# Edison_Mezzanine_I2C_Breakout.net
KiCad netlist of a schematic drawn in EAGLE
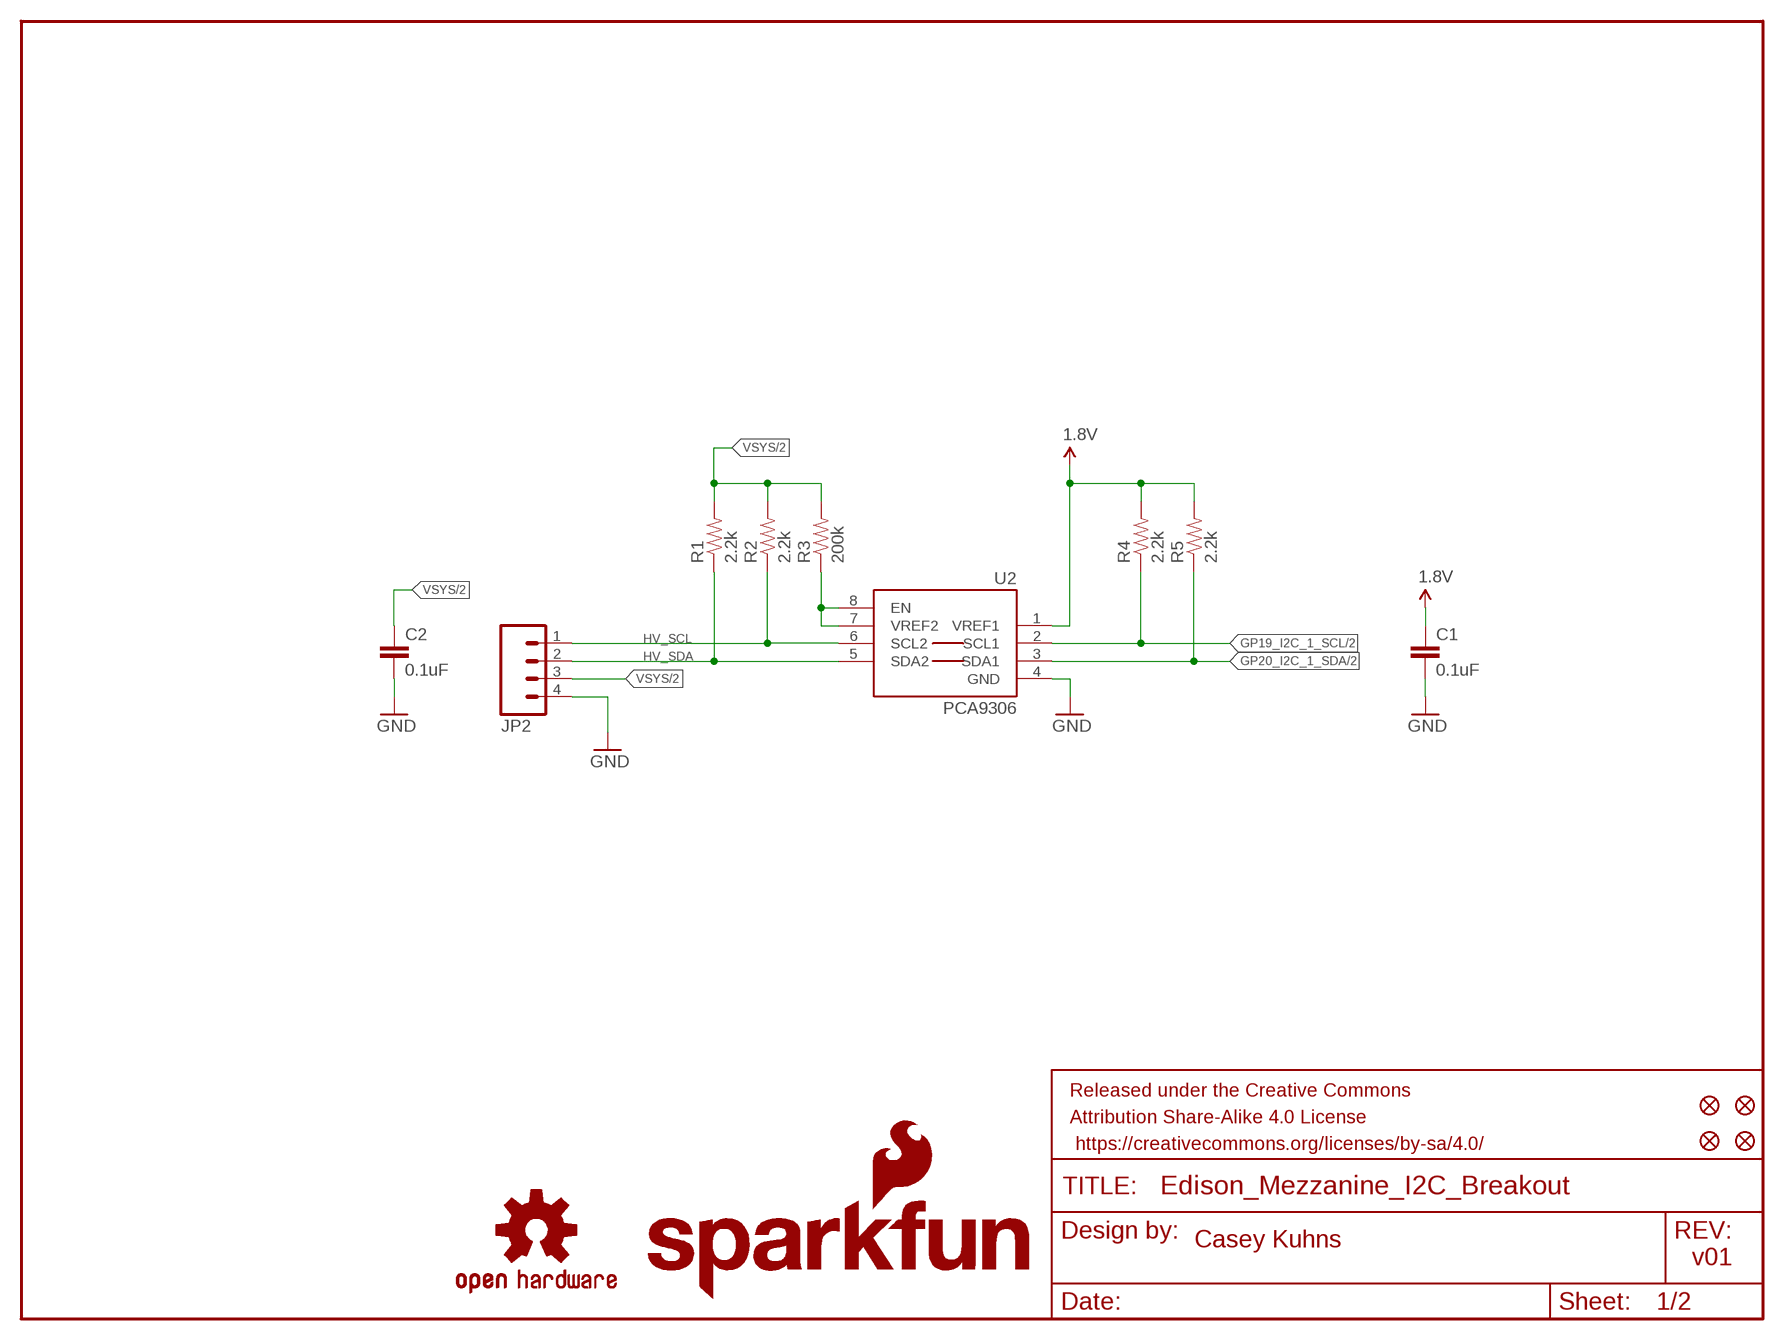
[diagram p0: schematic, sheet 1]
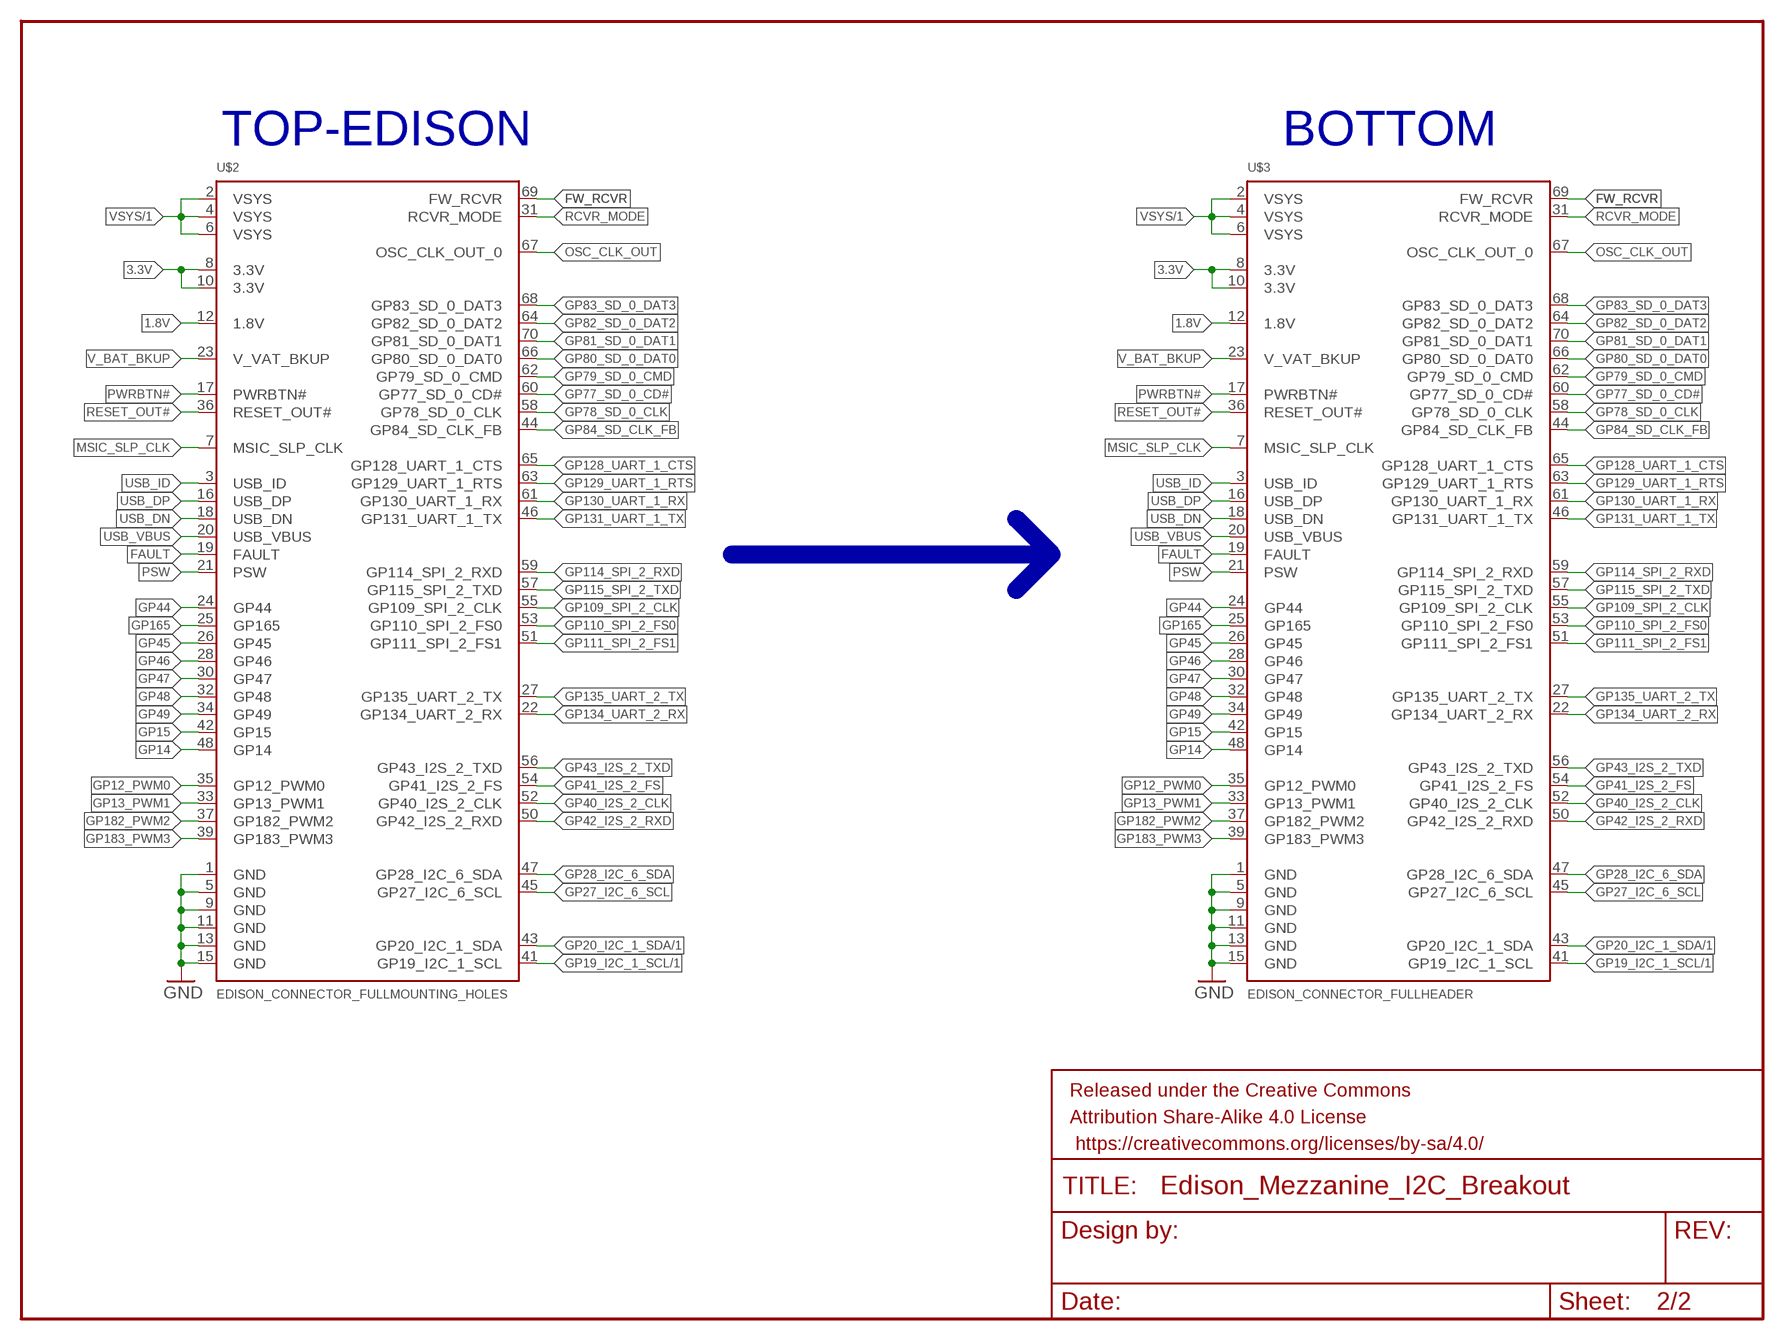
[diagram p1: schematic, sheet 2]

(export (version "E")
  (design (tool "Eeschema 10.0.6"))
  (components
    (comp (ref "C1")
      (value "0.1uF")
      (footprint "eagle-import:0603-CAP")
      (libsource (lib "eagle-import") (part "0.1UF-25V(+80/-20%)(0603)"))
    )
    (comp (ref "C2")
      (value "0.1uF")
      (footprint "eagle-import:0603-CAP")
      (libsource (lib "eagle-import") (part "0.1UF-25V(+80/-20%)(0603)"))
    )
    (comp (ref "FID1")
      (value "FIDUCIAL1X2")
      (footprint "eagle-import:FIDUCIAL-1X2")
      (libsource (lib "eagle-import") (part "FIDUCIAL1X2"))
    )
    (comp (ref "FID2")
      (value "FIDUCIAL1X2")
      (footprint "eagle-import:FIDUCIAL-1X2")
      (libsource (lib "eagle-import") (part "FIDUCIAL1X2"))
    )
    (comp (ref "FID3")
      (value "FIDUCIAL1X2")
      (footprint "eagle-import:FIDUCIAL-1X2")
      (libsource (lib "eagle-import") (part "FIDUCIAL1X2"))
    )
    (comp (ref "FID4")
      (value "FIDUCIAL1X2")
      (footprint "eagle-import:FIDUCIAL-1X2")
      (libsource (lib "eagle-import") (part "FIDUCIAL1X2"))
    )
    (comp (ref "FRAME1")
      (value "FRAME-LETTER")
      (footprint "eagle-import:CREATIVE_COMMONS")
      (libsource (lib "eagle-import") (part "FRAME-LETTER"))
    )
    (comp (ref "JP2")
      (value "M04SMD_RA_FEMALE")
      (footprint "eagle-import:1X04_SMD_RA_FEMALE")
      (libsource (lib "eagle-import") (part "M04SMD_RA_FEMALE"))
    )
    (comp (ref "LOGO1")
      (value "SFE_LOGO_NAME_FLAME.1_INCH")
      (footprint "eagle-import:SFE_LOGO_NAME_FLAME_.1")
      (libsource (lib "eagle-import") (part "SFE_LOGO_NAME_FLAME.1_INCH"))
    )
    (comp (ref "LOGO2")
      (value "OSHW-LOGOS")
      (footprint "eagle-import:OSHW-LOGO-S")
      (libsource (lib "eagle-import") (part "OSHW-LOGOS"))
    )
    (comp (ref "LOGO3")
      (value "SFE_LOGO_NAME_FLAME.1_INCH")
      (footprint "eagle-import:SFE_LOGO_NAME_FLAME_.1")
      (libsource (lib "eagle-import") (part "SFE_LOGO_NAME_FLAME.1_INCH"))
    )
    (comp (ref "LOGO4")
      (value "OSHW-LOGOS")
      (footprint "eagle-import:OSHW-LOGO-S")
      (libsource (lib "eagle-import") (part "OSHW-LOGOS"))
    )
    (comp (ref "R1")
      (value "2.2k")
      (footprint "eagle-import:0603-RES")
      (libsource (lib "eagle-import") (part "2.2KOHM1/10W1%(0603)"))
    )
    (comp (ref "R2")
      (value "2.2k")
      (footprint "eagle-import:0603-RES")
      (libsource (lib "eagle-import") (part "2.2KOHM1/10W1%(0603)"))
    )
    (comp (ref "R3")
      (value "200k")
      (footprint "eagle-import:0603-RES")
      (libsource (lib "eagle-import") (part "200KOHM1/10W1%(0603)200K"))
    )
    (comp (ref "R4")
      (value "2.2k")
      (footprint "eagle-import:0603-RES")
      (libsource (lib "eagle-import") (part "2.2KOHM1/10W1%(0603)"))
    )
    (comp (ref "R5")
      (value "2.2k")
      (footprint "eagle-import:0603-RES")
      (libsource (lib "eagle-import") (part "2.2KOHM1/10W1%(0603)"))
    )
    (comp (ref "U2")
      (value "PCA9306")
      (footprint "eagle-import:PCA9306DC-1_1")
      (libsource (lib "eagle-import") (part "PCA9306PCA9306DC-1{colon}1"))
    )
    (comp (ref "FRAME2")
      (value "FRAME-LETTER")
      (footprint "eagle-import:CREATIVE_COMMONS")
      (libsource (lib "eagle-import") (part "FRAME-LETTER"))
    )
    (comp (ref "U$2")
      (value "EDISON_CONNECTOR_FULLMOUNTING_HOLES")
      (footprint "eagle-import:EDISON_DAUGHTER")
      (libsource (lib "eagle-import") (part "EDISON_CONNECTOR_FULLMOUNTING_HOLES"))
    )
    (comp (ref "U$3")
      (value "EDISON_CONNECTOR_FULLHEADER")
      (footprint "eagle-import:DF40C-70DP-0.4(51)")
      (libsource (lib "eagle-import") (part "EDISON_CONNECTOR_FULLHEADER"))
    )
  )
  (nets
    (net (code "1") (name "1.8V") (class "Default")
      (node (ref "C1") (pin "1") (pinfunction "1_1") (pintype "passive"))
      (node (ref "R4") (pin "2") (pinfunction "2_2") (pintype "passive"))
      (node (ref "R5") (pin "2") (pinfunction "2_2") (pintype "passive"))
      (node (ref "U$2") (pin "12") (pinfunction "1.8V_12") (pintype "bidirectional"))
      (node (ref "U$3") (pin "12") (pinfunction "1.8V_12") (pintype "bidirectional"))
      (node (ref "U2") (pin "1") (pinfunction "VREF1_1") (pintype "bidirectional"))
    )
    (net (code "2") (name "3.3V") (class "Default")
      (node (ref "U$2") (pin "10") (pinfunction "3.3V_10") (pintype "bidirectional"))
      (node (ref "U$2") (pin "8") (pinfunction "3.3V_8") (pintype "bidirectional"))
      (node (ref "U$3") (pin "10") (pinfunction "3.3V_10") (pintype "bidirectional"))
      (node (ref "U$3") (pin "8") (pinfunction "3.3V_8") (pintype "bidirectional"))
    )
    (net (code "3") (name "FAULT") (class "Default")
      (node (ref "U$2") (pin "19") (pinfunction "FAULT_19") (pintype "bidirectional"))
      (node (ref "U$3") (pin "19") (pinfunction "FAULT_19") (pintype "bidirectional"))
    )
    (net (code "4") (name "FW_RCVR") (class "Default")
      (node (ref "U$2") (pin "69") (pinfunction "FW_RCVR_69") (pintype "bidirectional"))
      (node (ref "U$3") (pin "69") (pinfunction "FW_RCVR_69") (pintype "bidirectional"))
    )
    (net (code "5") (name "GND") (class "Default")
      (node (ref "C1") (pin "2") (pinfunction "2_2") (pintype "passive"))
      (node (ref "C2") (pin "2") (pinfunction "2_2") (pintype "passive"))
      (node (ref "JP2") (pin "4") (pinfunction "4_4") (pintype "passive"))
      (node (ref "U$2") (pin "1") (pinfunction "GND_1") (pintype "bidirectional"))
      (node (ref "U$2") (pin "11") (pinfunction "GND_11") (pintype "bidirectional"))
      (node (ref "U$2") (pin "13") (pinfunction "GND_13") (pintype "bidirectional"))
      (node (ref "U$2") (pin "15") (pinfunction "GND_15") (pintype "bidirectional"))
      (node (ref "U$2") (pin "5") (pinfunction "GND_5") (pintype "bidirectional"))
      (node (ref "U$2") (pin "9") (pinfunction "GND_9") (pintype "bidirectional"))
      (node (ref "U$3") (pin "1") (pinfunction "GND_1") (pintype "bidirectional"))
      (node (ref "U$3") (pin "11") (pinfunction "GND_11") (pintype "bidirectional"))
      (node (ref "U$3") (pin "13") (pinfunction "GND_13") (pintype "bidirectional"))
      (node (ref "U$3") (pin "15") (pinfunction "GND_15") (pintype "bidirectional"))
      (node (ref "U$3") (pin "5") (pinfunction "GND_5") (pintype "bidirectional"))
      (node (ref "U$3") (pin "9") (pinfunction "GND_9") (pintype "bidirectional"))
      (node (ref "U2") (pin "4") (pinfunction "GND_4") (pintype "bidirectional"))
    )
    (net (code "6") (name "GP12_PWM0") (class "Default")
      (node (ref "U$2") (pin "35") (pinfunction "GP12_PWM0_35") (pintype "bidirectional"))
      (node (ref "U$3") (pin "35") (pinfunction "GP12_PWM0_35") (pintype "bidirectional"))
    )
    (net (code "7") (name "GP13_PWM1") (class "Default")
      (node (ref "U$2") (pin "33") (pinfunction "GP13_PWM1_33") (pintype "bidirectional"))
      (node (ref "U$3") (pin "33") (pinfunction "GP13_PWM1_33") (pintype "bidirectional"))
    )
    (net (code "8") (name "GP14") (class "Default")
      (node (ref "U$2") (pin "48") (pinfunction "GP14_48") (pintype "bidirectional"))
      (node (ref "U$3") (pin "48") (pinfunction "GP14_48") (pintype "bidirectional"))
    )
    (net (code "9") (name "GP15") (class "Default")
      (node (ref "U$2") (pin "42") (pinfunction "GP15_42") (pintype "bidirectional"))
      (node (ref "U$3") (pin "42") (pinfunction "GP15_42") (pintype "bidirectional"))
    )
    (net (code "10") (name "GP19_I2C_1_SCL") (class "Default")
      (node (ref "R4") (pin "1") (pinfunction "1_1") (pintype "passive"))
      (node (ref "U$2") (pin "41") (pinfunction "GP19_I2C_1_SCL_41") (pintype "bidirectional"))
      (node (ref "U$3") (pin "41") (pinfunction "GP19_I2C_1_SCL_41") (pintype "bidirectional"))
      (node (ref "U2") (pin "2") (pinfunction "SCL1_2") (pintype "bidirectional"))
    )
    (net (code "11") (name "GP20_I2C_1_SDA") (class "Default")
      (node (ref "R5") (pin "1") (pinfunction "1_1") (pintype "passive"))
      (node (ref "U$2") (pin "43") (pinfunction "GP20_I2C_1_SDA_43") (pintype "bidirectional"))
      (node (ref "U$3") (pin "43") (pinfunction "GP20_I2C_1_SDA_43") (pintype "bidirectional"))
      (node (ref "U2") (pin "3") (pinfunction "SDA1_3") (pintype "bidirectional"))
    )
    (net (code "12") (name "GP27_I2C_6_SCL") (class "Default")
      (node (ref "U$2") (pin "45") (pinfunction "GP27_I2C_6_SCL_45") (pintype "bidirectional"))
      (node (ref "U$3") (pin "45") (pinfunction "GP27_I2C_6_SCL_45") (pintype "bidirectional"))
    )
    (net (code "13") (name "GP28_I2C_6_SDA") (class "Default")
      (node (ref "U$2") (pin "47") (pinfunction "GP28_I2C_6_SDA_47") (pintype "bidirectional"))
      (node (ref "U$3") (pin "47") (pinfunction "GP28_I2C_6_SDA_47") (pintype "bidirectional"))
    )
    (net (code "14") (name "GP40_I2S_2_CLK") (class "Default")
      (node (ref "U$2") (pin "52") (pinfunction "GP40_I2S_2_CLK_52") (pintype "bidirectional"))
      (node (ref "U$3") (pin "52") (pinfunction "GP40_I2S_2_CLK_52") (pintype "bidirectional"))
    )
    (net (code "15") (name "GP41_I2S_2_FS") (class "Default")
      (node (ref "U$2") (pin "54") (pinfunction "GP41_I2S_2_FS_54") (pintype "bidirectional"))
      (node (ref "U$3") (pin "54") (pinfunction "GP41_I2S_2_FS_54") (pintype "bidirectional"))
    )
    (net (code "16") (name "GP42_I2S_2_RXD") (class "Default")
      (node (ref "U$2") (pin "50") (pinfunction "GP42_I2S_2_RXD_50") (pintype "bidirectional"))
      (node (ref "U$3") (pin "50") (pinfunction "GP42_I2S_2_RXD_50") (pintype "bidirectional"))
    )
    (net (code "17") (name "GP43_I2S_2_TXD") (class "Default")
      (node (ref "U$2") (pin "56") (pinfunction "GP43_I2S_2_TXD_56") (pintype "bidirectional"))
      (node (ref "U$3") (pin "56") (pinfunction "GP43_I2S_2_TXD_56") (pintype "bidirectional"))
    )
    (net (code "18") (name "GP44") (class "Default")
      (node (ref "U$2") (pin "24") (pinfunction "GP44_24") (pintype "bidirectional"))
      (node (ref "U$3") (pin "24") (pinfunction "GP44_24") (pintype "bidirectional"))
    )
    (net (code "19") (name "GP45") (class "Default")
      (node (ref "U$2") (pin "26") (pinfunction "GP45_26") (pintype "bidirectional"))
      (node (ref "U$3") (pin "26") (pinfunction "GP45_26") (pintype "bidirectional"))
    )
    (net (code "20") (name "GP46") (class "Default")
      (node (ref "U$2") (pin "28") (pinfunction "GP46_28") (pintype "bidirectional"))
      (node (ref "U$3") (pin "28") (pinfunction "GP46_28") (pintype "bidirectional"))
    )
    (net (code "21") (name "GP47") (class "Default")
      (node (ref "U$2") (pin "30") (pinfunction "GP47_30") (pintype "bidirectional"))
      (node (ref "U$3") (pin "30") (pinfunction "GP47_30") (pintype "bidirectional"))
    )
    (net (code "22") (name "GP48") (class "Default")
      (node (ref "U$2") (pin "32") (pinfunction "GP48_32") (pintype "bidirectional"))
      (node (ref "U$3") (pin "32") (pinfunction "GP48_32") (pintype "bidirectional"))
    )
    (net (code "23") (name "GP49") (class "Default")
      (node (ref "U$2") (pin "34") (pinfunction "GP49_34") (pintype "bidirectional"))
      (node (ref "U$3") (pin "34") (pinfunction "GP49_34") (pintype "bidirectional"))
    )
    (net (code "24") (name "GP77_SD_0_CD#") (class "Default")
      (node (ref "U$2") (pin "60") (pinfunction "GP77_SD_0_CD#_60") (pintype "bidirectional"))
      (node (ref "U$3") (pin "60") (pinfunction "GP77_SD_0_CD#_60") (pintype "bidirectional"))
    )
    (net (code "25") (name "GP78_SD_0_CLK") (class "Default")
      (node (ref "U$2") (pin "58") (pinfunction "GP78_SD_0_CLK_58") (pintype "bidirectional"))
      (node (ref "U$3") (pin "58") (pinfunction "GP78_SD_0_CLK_58") (pintype "bidirectional"))
    )
    (net (code "26") (name "GP79_SD_0_CMD") (class "Default")
      (node (ref "U$2") (pin "62") (pinfunction "GP79_SD_0_CMD_62") (pintype "bidirectional"))
      (node (ref "U$3") (pin "62") (pinfunction "GP79_SD_0_CMD_62") (pintype "bidirectional"))
    )
    (net (code "27") (name "GP80_SD_0_DAT0") (class "Default")
      (node (ref "U$2") (pin "66") (pinfunction "GP80_SD_0_DAT0_66") (pintype "bidirectional"))
      (node (ref "U$3") (pin "66") (pinfunction "GP80_SD_0_DAT0_66") (pintype "bidirectional"))
    )
    (net (code "28") (name "GP81_SD_0_DAT1") (class "Default")
      (node (ref "U$2") (pin "70") (pinfunction "GP81_SD_0_DAT1_70") (pintype "bidirectional"))
      (node (ref "U$3") (pin "70") (pinfunction "GP81_SD_0_DAT1_70") (pintype "bidirectional"))
    )
    (net (code "29") (name "GP82_SD_0_DAT2") (class "Default")
      (node (ref "U$2") (pin "64") (pinfunction "GP82_SD_0_DAT2_64") (pintype "bidirectional"))
      (node (ref "U$3") (pin "64") (pinfunction "GP82_SD_0_DAT2_64") (pintype "bidirectional"))
    )
    (net (code "30") (name "GP83_SD_0_DAT3") (class "Default")
      (node (ref "U$2") (pin "68") (pinfunction "GP83_SD_0_DAT3_68") (pintype "bidirectional"))
      (node (ref "U$3") (pin "68") (pinfunction "GP83_SD_0_DAT3_68") (pintype "bidirectional"))
    )
    (net (code "31") (name "GP84_SD_CLK_FB") (class "Default")
      (node (ref "U$2") (pin "44") (pinfunction "GP84_SD_CLK_FB_44") (pintype "bidirectional"))
      (node (ref "U$3") (pin "44") (pinfunction "GP84_SD_CLK_FB_44") (pintype "bidirectional"))
    )
    (net (code "32") (name "GP109_SPI_2_CLK") (class "Default")
      (node (ref "U$2") (pin "55") (pinfunction "GP109_SPI_2_CLK_55") (pintype "bidirectional"))
      (node (ref "U$3") (pin "55") (pinfunction "GP109_SPI_2_CLK_55") (pintype "bidirectional"))
    )
    (net (code "33") (name "GP110_SPI_2_FS0") (class "Default")
      (node (ref "U$2") (pin "53") (pinfunction "GP110_SPI_2_FS0_53") (pintype "bidirectional"))
      (node (ref "U$3") (pin "53") (pinfunction "GP110_SPI_2_FS0_53") (pintype "bidirectional"))
    )
    (net (code "34") (name "GP111_SPI_2_FS1") (class "Default")
      (node (ref "U$2") (pin "51") (pinfunction "GP111_SPI_2_FS1_51") (pintype "bidirectional"))
      (node (ref "U$3") (pin "51") (pinfunction "GP111_SPI_2_FS1_51") (pintype "bidirectional"))
    )
    (net (code "35") (name "GP114_SPI_2_RXD") (class "Default")
      (node (ref "U$2") (pin "59") (pinfunction "GP114_SPI_2_RXD_59") (pintype "bidirectional"))
      (node (ref "U$3") (pin "59") (pinfunction "GP114_SPI_2_RXD_59") (pintype "bidirectional"))
    )
    (net (code "36") (name "GP115_SPI_2_TXD") (class "Default")
      (node (ref "U$2") (pin "57") (pinfunction "GP115_SPI_2_TXD_57") (pintype "bidirectional"))
      (node (ref "U$3") (pin "57") (pinfunction "GP115_SPI_2_TXD_57") (pintype "bidirectional"))
    )
    (net (code "37") (name "GP128_UART_1_CTS") (class "Default")
      (node (ref "U$2") (pin "65") (pinfunction "GP128_UART_1_CTS_65") (pintype "bidirectional"))
      (node (ref "U$3") (pin "65") (pinfunction "GP128_UART_1_CTS_65") (pintype "bidirectional"))
    )
    (net (code "38") (name "GP129_UART_1_RTS") (class "Default")
      (node (ref "U$2") (pin "63") (pinfunction "GP129_UART_1_RTS_63") (pintype "bidirectional"))
      (node (ref "U$3") (pin "63") (pinfunction "GP129_UART_1_RTS_63") (pintype "bidirectional"))
    )
    (net (code "39") (name "GP130_UART_1_RX") (class "Default")
      (node (ref "U$2") (pin "61") (pinfunction "GP130_UART_1_RX_61") (pintype "bidirectional"))
      (node (ref "U$3") (pin "61") (pinfunction "GP130_UART_1_RX_61") (pintype "bidirectional"))
    )
    (net (code "40") (name "GP131_UART_1_TX") (class "Default")
      (node (ref "U$2") (pin "46") (pinfunction "GP131_UART_1_TX_46") (pintype "bidirectional"))
      (node (ref "U$3") (pin "46") (pinfunction "GP131_UART_1_TX_46") (pintype "bidirectional"))
    )
    (net (code "41") (name "GP134_UART_2_RX") (class "Default")
      (node (ref "U$2") (pin "22") (pinfunction "GP134_UART_2_RX_22") (pintype "bidirectional"))
      (node (ref "U$3") (pin "22") (pinfunction "GP134_UART_2_RX_22") (pintype "bidirectional"))
    )
    (net (code "42") (name "GP135_UART_2_TX") (class "Default")
      (node (ref "U$2") (pin "27") (pinfunction "GP135_UART_2_TX_27") (pintype "bidirectional"))
      (node (ref "U$3") (pin "27") (pinfunction "GP135_UART_2_TX_27") (pintype "bidirectional"))
    )
    (net (code "43") (name "GP165") (class "Default")
      (node (ref "U$2") (pin "25") (pinfunction "GP165_25") (pintype "bidirectional"))
      (node (ref "U$3") (pin "25") (pinfunction "GP165_25") (pintype "bidirectional"))
    )
    (net (code "44") (name "GP182_PWM2") (class "Default")
      (node (ref "U$2") (pin "37") (pinfunction "GP182_PWM2_37") (pintype "bidirectional"))
      (node (ref "U$3") (pin "37") (pinfunction "GP182_PWM2_37") (pintype "bidirectional"))
    )
    (net (code "45") (name "GP183_PWM3") (class "Default")
      (node (ref "U$2") (pin "39") (pinfunction "GP183_PWM3_39") (pintype "bidirectional"))
      (node (ref "U$3") (pin "39") (pinfunction "GP183_PWM3_39") (pintype "bidirectional"))
    )
    (net (code "46") (name "HV_SCL") (class "Default")
      (node (ref "JP2") (pin "1") (pinfunction "1_1") (pintype "passive"))
      (node (ref "R2") (pin "1") (pinfunction "1_1") (pintype "passive"))
      (node (ref "U2") (pin "6") (pinfunction "SCL2_6") (pintype "bidirectional"))
    )
    (net (code "47") (name "HV_SDA") (class "Default")
      (node (ref "JP2") (pin "2") (pinfunction "2_2") (pintype "passive"))
      (node (ref "R1") (pin "1") (pinfunction "1_1") (pintype "passive"))
      (node (ref "U2") (pin "5") (pinfunction "SDA2_5") (pintype "bidirectional"))
    )
    (net (code "48") (name "MSIC_SLP_CLK") (class "Default")
      (node (ref "U$2") (pin "7") (pinfunction "MSIC_SLP_CLK_7") (pintype "bidirectional"))
      (node (ref "U$3") (pin "7") (pinfunction "MSIC_SLP_CLK_7") (pintype "bidirectional"))
    )
    (net (code "49") (name "Net-(U2-EN)") (class "Default")
      (node (ref "R3") (pin "1") (pinfunction "1_1") (pintype "passive"))
      (node (ref "U2") (pin "7") (pinfunction "VREF2_7") (pintype "bidirectional"))
      (node (ref "U2") (pin "8") (pinfunction "EN_8") (pintype "bidirectional"))
    )
    (net (code "50") (name "OSC_CLK_OUT") (class "Default")
      (node (ref "U$2") (pin "67") (pinfunction "OSC_CLK_OUT_0_67") (pintype "bidirectional"))
      (node (ref "U$3") (pin "67") (pinfunction "OSC_CLK_OUT_0_67") (pintype "bidirectional"))
    )
    (net (code "51") (name "PSW") (class "Default")
      (node (ref "U$2") (pin "21") (pinfunction "PSW_21") (pintype "bidirectional"))
      (node (ref "U$3") (pin "21") (pinfunction "PSW_21") (pintype "bidirectional"))
    )
    (net (code "52") (name "PWRBTN#") (class "Default")
      (node (ref "U$2") (pin "17") (pinfunction "PWRBTN#_17") (pintype "bidirectional"))
      (node (ref "U$3") (pin "17") (pinfunction "PWRBTN#_17") (pintype "bidirectional"))
    )
    (net (code "53") (name "RCVR_MODE") (class "Default")
      (node (ref "U$2") (pin "31") (pinfunction "RCVR_MODE_31") (pintype "bidirectional"))
      (node (ref "U$3") (pin "31") (pinfunction "RCVR_MODE_31") (pintype "bidirectional"))
    )
    (net (code "54") (name "RESET_OUT#") (class "Default")
      (node (ref "U$2") (pin "36") (pinfunction "RESET_OUT#_36") (pintype "bidirectional"))
      (node (ref "U$3") (pin "36") (pinfunction "RESET_OUT#_36") (pintype "bidirectional"))
    )
    (net (code "55") (name "USB_DN") (class "Default")
      (node (ref "U$2") (pin "18") (pinfunction "USB_DN_18") (pintype "bidirectional"))
      (node (ref "U$3") (pin "18") (pinfunction "USB_DN_18") (pintype "bidirectional"))
    )
    (net (code "56") (name "USB_DP") (class "Default")
      (node (ref "U$2") (pin "16") (pinfunction "USB_DP_16") (pintype "bidirectional"))
      (node (ref "U$3") (pin "16") (pinfunction "USB_DP_16") (pintype "bidirectional"))
    )
    (net (code "57") (name "USB_ID") (class "Default")
      (node (ref "U$2") (pin "3") (pinfunction "USB_ID_3") (pintype "bidirectional"))
      (node (ref "U$3") (pin "3") (pinfunction "USB_ID_3") (pintype "bidirectional"))
    )
    (net (code "58") (name "USB_VBUS") (class "Default")
      (node (ref "U$2") (pin "20") (pinfunction "USB_VBUS_20") (pintype "bidirectional"))
      (node (ref "U$3") (pin "20") (pinfunction "USB_VBUS_20") (pintype "bidirectional"))
    )
    (net (code "59") (name "VSYS") (class "Default")
      (node (ref "C2") (pin "1") (pinfunction "1_1") (pintype "passive"))
      (node (ref "JP2") (pin "3") (pinfunction "3_3") (pintype "passive"))
      (node (ref "R1") (pin "2") (pinfunction "2_2") (pintype "passive"))
      (node (ref "R2") (pin "2") (pinfunction "2_2") (pintype "passive"))
      (node (ref "R3") (pin "2") (pinfunction "2_2") (pintype "passive"))
      (node (ref "U$2") (pin "2") (pinfunction "VSYS_2") (pintype "bidirectional"))
      (node (ref "U$2") (pin "4") (pinfunction "VSYS_4") (pintype "bidirectional"))
      (node (ref "U$2") (pin "6") (pinfunction "VSYS_6") (pintype "bidirectional"))
      (node (ref "U$3") (pin "2") (pinfunction "VSYS_2") (pintype "bidirectional"))
      (node (ref "U$3") (pin "4") (pinfunction "VSYS_4") (pintype "bidirectional"))
      (node (ref "U$3") (pin "6") (pinfunction "VSYS_6") (pintype "bidirectional"))
    )
    (net (code "60") (name "V_BAT_BKUP") (class "Default")
      (node (ref "U$2") (pin "23") (pinfunction "V_VAT_BKUP_23") (pintype "bidirectional"))
      (node (ref "U$3") (pin "23") (pinfunction "V_VAT_BKUP_23") (pintype "bidirectional"))
    )
  )
)
